# 12to5.net
KiCad netlist of a schematic drawn in Altium Designer
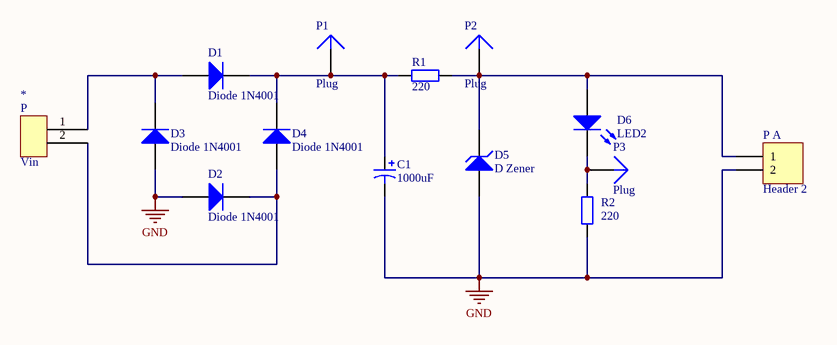
[diagram p0: 12to5.SchDoc]

(export (version "E")
  (design (tool "Eeschema 10.0.6"))
  (components
    (comp (ref "*")
      (value "Vin")
      (footprint "PCBComponent_1")
      (libsource (lib "Universitatea Stefan Cel Mare Suceava") (part "Component_1"))
    )
    (comp (ref "C1")
      (value "1000uF")
      (footprint "RB7.6-15")
      (description "Polarized Capacitor (Radial)")
      (fields (field (name "Comment") "Cap Pol1") (field (name "PUBLISHER") "Altium Limited"))
      (libsource (lib "Universitatea Stefan Cel Mare Suceava") (part "Cap Pol3"))
    )
    (comp (ref "D1")
      (value "Diode 1N4001")
      (footprint "DO-41")
      (description "1 Amp General Purpose Rectifier")
      (fields (field (name "PUBLISHER") "Altium Limited"))
      (libsource (lib "Universitatea Stefan Cel Mare Suceava") (part "Diode 1N5408"))
    )
    (comp (ref "D2")
      (value "Diode 1N4001")
      (footprint "DO-41")
      (description "1 Amp General Purpose Rectifier")
      (fields (field (name "PUBLISHER") "Altium Limited"))
      (libsource (lib "Universitatea Stefan Cel Mare Suceava") (part "Diode 1N5408"))
    )
    (comp (ref "D3")
      (value "Diode 1N4001")
      (footprint "DO-41")
      (description "1 Amp General Purpose Rectifier")
      (fields (field (name "PUBLISHER") "Altium Limited"))
      (libsource (lib "Universitatea Stefan Cel Mare Suceava") (part "Diode 1N5408"))
    )
    (comp (ref "D4")
      (value "Diode 1N4001")
      (footprint "DO-41")
      (description "1 Amp General Purpose Rectifier")
      (fields (field (name "PUBLISHER") "Altium Limited"))
      (libsource (lib "Universitatea Stefan Cel Mare Suceava") (part "Diode 1N5408"))
    )
    (comp (ref "D5")
      (value "D Zener")
      (footprint "DIODE-0.7")
      (description "Zener Diode")
      (fields (field (name "PUBLISHER") "Altium Limited"))
      (libsource (lib "Universitatea Stefan Cel Mare Suceava") (part "D Zener"))
    )
    (comp (ref "D6")
      (value "LED2")
      (footprint "3.2X1.6X1.1")
      (description "Typical RED, GREEN, YELLOW, AMBER GaAs LED")
      (fields (field (name "PUBLISHER") "Altium Limited"))
      (libsource (lib "Universitatea Stefan Cel Mare Suceava") (part "LED3"))
    )
    (comp (ref "P A")
      (value "Header 2")
      (footprint "HDR1X2")
      (description "Header, 2-Pin")
      (fields (field (name "PUBLISHER") "Altium Limited"))
      (libsource (lib "Universitatea Stefan Cel Mare Suceava") (part "Header 2H"))
    )
    (comp (ref "P1")
      (value "Plug")
      (footprint "PIN1")
      (fields (field (name "PUBLISHER") "Altium Limited"))
      (libsource (lib "Universitatea Stefan Cel Mare Suceava") (part "Plug"))
    )
    (comp (ref "P2")
      (value "Plug")
      (footprint "PIN1")
      (fields (field (name "PUBLISHER") "Altium Limited"))
      (libsource (lib "Universitatea Stefan Cel Mare Suceava") (part "Plug"))
    )
    (comp (ref "P3")
      (value "Plug")
      (footprint "PIN1")
      (fields (field (name "PUBLISHER") "Altium Limited"))
      (libsource (lib "Universitatea Stefan Cel Mare Suceava") (part "Plug"))
    )
    (comp (ref "R1")
      (value "220")
      (footprint "AXIAL-0.4")
      (description "Resistor")
      (fields (field (name "Comment") "Res2") (field (name "PUBLISHER") "Altium Limited"))
      (libsource (lib "") (part "Res2_1"))
    )
    (comp (ref "R2")
      (value "220")
      (footprint "AXIAL-0.4")
      (description "Resistor")
      (fields (field (name "Comment") "Res2") (field (name "PUBLISHER") "Altium Limited"))
      (libsource (lib "Universitatea Stefan Cel Mare Suceava") (part "Res2"))
    )
  )
  (nets
    (net (code "1") (name "GND") (class "Default")
      (node (ref "C1") (pin "2") (pinfunction "2_2") (pintype "passive"))
      (node (ref "D2") (pin "1") (pinfunction "A_1") (pintype "passive"))
      (node (ref "D3") (pin "1") (pinfunction "A_1") (pintype "passive"))
      (node (ref "D5") (pin "1") (pinfunction "A_1") (pintype "passive"))
      (node (ref "P A") (pin "2") (pinfunction "2_2") (pintype "passive"))
      (node (ref "R2") (pin "1") (pinfunction "1_1") (pintype "passive"))
    )
    (net (code "2") (name "Net-(D1-A)") (class "Default")
      (node (ref "*") (pin "1") (pinfunction "1_1") (pintype "passive"))
      (node (ref "D1") (pin "1") (pinfunction "A_1") (pintype "passive"))
      (node (ref "D3") (pin "2") (pinfunction "K_2") (pintype "passive"))
    )
    (net (code "3") (name "Net-(D1-K)") (class "Default")
      (node (ref "C1") (pin "1") (pinfunction "1_1") (pintype "passive"))
      (node (ref "D1") (pin "2") (pinfunction "K_2") (pintype "passive"))
      (node (ref "D4") (pin "2") (pinfunction "K_2") (pintype "passive"))
      (node (ref "P1") (pin "1") (pinfunction "1_1") (pintype "passive"))
      (node (ref "R1") (pin "1") (pinfunction "1_1") (pintype "passive"))
    )
    (net (code "4") (name "Net-(D2-K)") (class "Default")
      (node (ref "*") (pin "2") (pinfunction "2_2") (pintype "passive"))
      (node (ref "D2") (pin "2") (pinfunction "K_2") (pintype "passive"))
      (node (ref "D4") (pin "1") (pinfunction "A_1") (pintype "passive"))
    )
    (net (code "5") (name "Net-(D5-K)") (class "Default")
      (node (ref "D5") (pin "2") (pinfunction "K_2") (pintype "passive"))
      (node (ref "D6") (pin "1") (pinfunction "A_1") (pintype "passive"))
      (node (ref "P A") (pin "1") (pinfunction "1_1") (pintype "passive"))
      (node (ref "P2") (pin "1") (pinfunction "1_1") (pintype "passive"))
      (node (ref "R1") (pin "2") (pinfunction "2_2") (pintype "passive"))
    )
    (net (code "6") (name "Net-(D6-K)") (class "Default")
      (node (ref "D6") (pin "2") (pinfunction "K_2") (pintype "passive"))
      (node (ref "P3") (pin "1") (pinfunction "1_1") (pintype "passive"))
      (node (ref "R2") (pin "2") (pinfunction "2_2") (pintype "passive"))
    )
  )
)
